# ProPrj_usb__2025-12-14-12-29-49.net
KiCad netlist of a schematic drawn in EasyEDA Pro
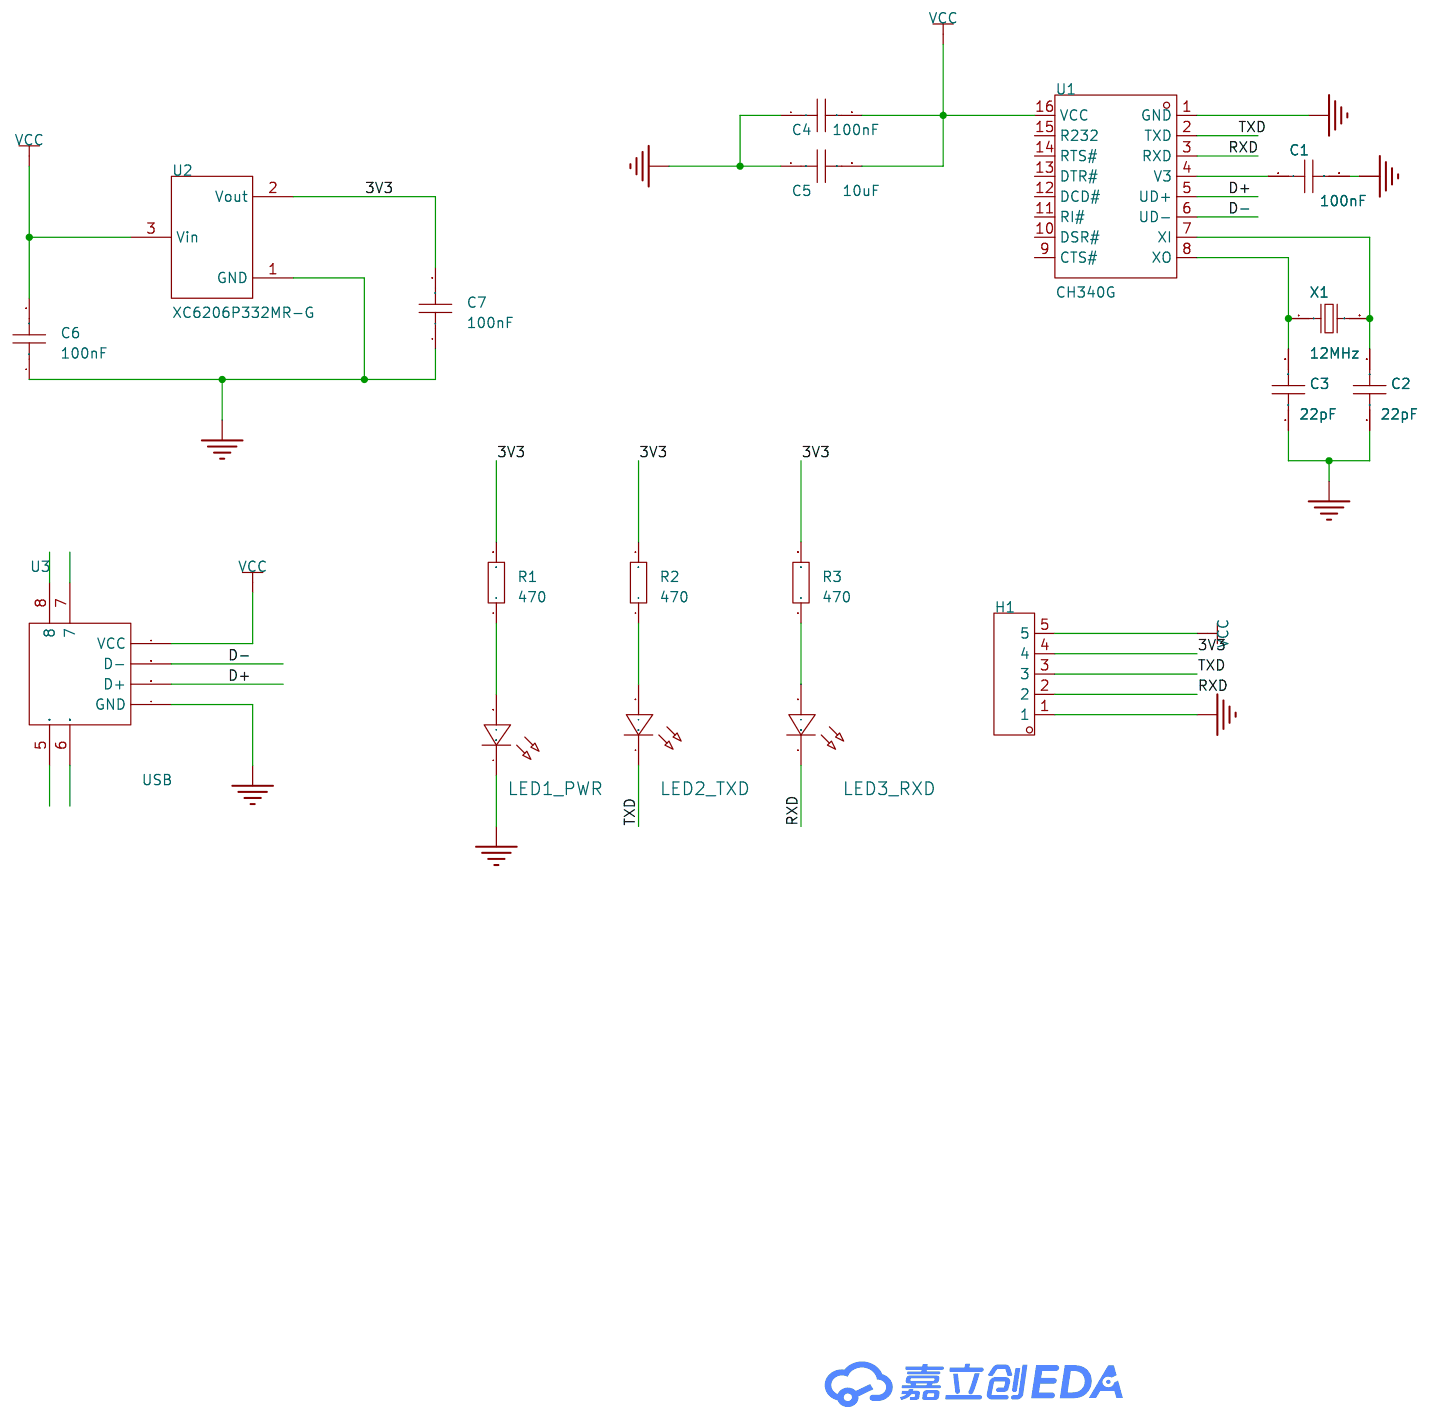
[diagram p0: schematic sheet]

(export (version "E")
  (design (tool "Eeschema 10.0.6"))
  (components
    (comp (ref "C1")
      (value "100nF")
      (footprint "easyedapro:C0603")
      (libsource (lib "easyedapro") (part "Capacitance"))
    )
    (comp (ref "C2")
      (value "22pF")
      (footprint "easyedapro:C0603")
      (libsource (lib "easyedapro") (part "Capacitance"))
    )
    (comp (ref "C3")
      (value "22pF")
      (footprint "easyedapro:C0603")
      (libsource (lib "easyedapro") (part "Capacitance"))
    )
    (comp (ref "C4")
      (value "100nF")
      (footprint "easyedapro:C0603")
      (libsource (lib "easyedapro") (part "Capacitance"))
    )
    (comp (ref "C5")
      (value "10uF")
      (footprint "easyedapro:C0603")
      (libsource (lib "easyedapro") (part "Capacitance"))
    )
    (comp (ref "C6")
      (value "100nF")
      (footprint "easyedapro:C0603")
      (libsource (lib "easyedapro") (part "Capacitance"))
    )
    (comp (ref "C7")
      (value "100nF")
      (footprint "easyedapro:C0603")
      (libsource (lib "easyedapro") (part "Capacitance"))
    )
    (comp (ref "H1")
      (value "~")
      (footprint "easyedapro:HDR-TH_5P-P2.54-V-M")
      (libsource (lib "easyedapro") (part "MTP125-1105S1"))
    )
    (comp (ref "LED1_PWR")
      (value "~")
      (footprint "easyedapro:LED_0603")
      (libsource (lib "easyedapro") (part "LED_R"))
    )
    (comp (ref "LED2_TXD")
      (value "~")
      (footprint "easyedapro:LED_0603")
      (libsource (lib "easyedapro") (part "LED_R"))
    )
    (comp (ref "LED3_RXD")
      (value "~")
      (footprint "easyedapro:LED_0603")
      (libsource (lib "easyedapro") (part "LED_R"))
    )
    (comp (ref "R1") (value "470") (footprint "easyedapro:R0603") (libsource (lib "easyedapro") (part "电阻")))
    (comp (ref "R2") (value "470") (footprint "easyedapro:R0603") (libsource (lib "easyedapro") (part "电阻")))
    (comp (ref "R3") (value "470") (footprint "easyedapro:R0603") (libsource (lib "easyedapro") (part "电阻")))
    (comp (ref "U1")
      (value "CH340G")
      (footprint "easyedapro:SOIC-16_L9.9-W3.9-P1.27-LS6.0-BL")
      (description "应用功能:USB转UART;接口协议:USB 2.0;数据速率:2Mbps;")
      (fields (field (name "Manufacturer") "WCH(南京沁恒)"))
      (libsource (lib "easyedapro") (part "CH340G"))
    )
    (comp (ref "U2")
      (value "XC6206P332MR-G")
      (footprint "easyedapro:SOT-23-3_L2.9-W1.6-P1.90-LS2.8-BR")
      (description "输出类型:固定;工作电压:6V;输出电压:3.3V;输出电流:200mA;电源纹波抑制比(PSRR):-;输出极性:正极;")
      (fields (field (name "Manufacturer") "TOREX(特瑞仕)"))
      (libsource (lib "easyedapro") (part "XC6206P332MR"))
    )
    (comp (ref "U3")
      (value "USB")
      (footprint "easyedapro:USB-SMD_USB_1")
      (libsource (lib "easyedapro") (part "USB"))
    )
    (comp (ref "X1")
      (value "12MHz")
      (footprint "easyedapro:CRYSTAL-SMD_L5.0-W3.2")
      (description "晶振类型:贴片晶振;频率:12MHz;常温频差:±20ppm;负载电容:20pF;频率稳定度:±30ppm;")
      (fields
        (field (name "Manufacturer Part") "XC53G2-12.000-F20LJDT")
        (field (name "Manufacturer") "HCI(杭晶)")
      )
      (libsource (lib "easyedapro") (part "XC53G2-12.000-F20LJDT"))
    )
  )
  (nets
    (net (code "1") (name "/3V3") (class "Default")
      (node (ref "C7") (pin "2") (pinfunction "2_2") (pintype "input"))
      (node (ref "H1") (pin "4") (pinfunction "4_4") (pintype "unspecified"))
      (node (ref "R1") (pin "2") (pinfunction "2_2") (pintype "input"))
      (node (ref "R2") (pin "2") (pinfunction "2_2") (pintype "input"))
      (node (ref "R3") (pin "2") (pinfunction "2_2") (pintype "input"))
      (node (ref "U2") (pin "2") (pinfunction "Vout_2") (pintype "unspecified"))
    )
    (net (code "2") (name "/D+") (class "Default")
      (node (ref "U1") (pin "5") (pinfunction "UD+_5") (pintype "unspecified"))
      (node (ref "U3") (pin "3") (pinfunction "D+_3") (pintype "input"))
    )
    (net (code "3") (name "/D-") (class "Default")
      (node (ref "U1") (pin "6") (pinfunction "UD-_6") (pintype "unspecified"))
      (node (ref "U3") (pin "2") (pinfunction "D-_2") (pintype "input"))
    )
    (net (code "4") (name "/RXD") (class "Default")
      (node (ref "H1") (pin "2") (pinfunction "2_2") (pintype "unspecified"))
      (node (ref "LED3_RXD") (pin "1") (pinfunction "C_1") (pintype "input"))
      (node (ref "U1") (pin "3") (pinfunction "RXD_3") (pintype "unspecified"))
    )
    (net (code "5") (name "/TXD") (class "Default")
      (node (ref "H1") (pin "3") (pinfunction "3_3") (pintype "unspecified"))
      (node (ref "LED2_TXD") (pin "1") (pinfunction "C_1") (pintype "input"))
      (node (ref "U1") (pin "2") (pinfunction "TXD_2") (pintype "unspecified"))
    )
    (net (code "6") (name "GND") (class "Default")
      (node (ref "C1") (pin "2") (pinfunction "2_2") (pintype "input"))
      (node (ref "C2") (pin "1") (pinfunction "1_1") (pintype "input"))
      (node (ref "C3") (pin "1") (pinfunction "1_1") (pintype "input"))
      (node (ref "C4") (pin "1") (pinfunction "1_1") (pintype "input"))
      (node (ref "C5") (pin "1") (pinfunction "1_1") (pintype "input"))
      (node (ref "C6") (pin "1") (pinfunction "1_1") (pintype "input"))
      (node (ref "C7") (pin "1") (pinfunction "1_1") (pintype "input"))
      (node (ref "H1") (pin "1") (pinfunction "1_1") (pintype "unspecified"))
      (node (ref "LED1_PWR") (pin "1") (pinfunction "C_1") (pintype "input"))
      (node (ref "U1") (pin "1") (pinfunction "GND_1") (pintype "unspecified"))
      (node (ref "U2") (pin "1") (pinfunction "GND_1") (pintype "unspecified"))
      (node (ref "U3") (pin "4") (pinfunction "GND_4") (pintype "input"))
    )
    (net (code "7") (name "Net-(LED1_PWR-A)") (class "Default")
      (node (ref "LED1_PWR") (pin "2") (pinfunction "A_2") (pintype "input"))
      (node (ref "R1") (pin "1") (pinfunction "1_1") (pintype "input"))
    )
    (net (code "8") (name "Net-(LED2_TXD-A)") (class "Default")
      (node (ref "LED2_TXD") (pin "2") (pinfunction "A_2") (pintype "input"))
      (node (ref "R2") (pin "1") (pinfunction "1_1") (pintype "input"))
    )
    (net (code "9") (name "Net-(LED3_RXD-A)") (class "Default")
      (node (ref "LED3_RXD") (pin "2") (pinfunction "A_2") (pintype "input"))
      (node (ref "R3") (pin "1") (pinfunction "1_1") (pintype "input"))
    )
    (net (code "10") (name "Net-(U1-V3)") (class "Default")
      (node (ref "C1") (pin "1") (pinfunction "1_1") (pintype "input"))
      (node (ref "U1") (pin "4") (pinfunction "V3_4") (pintype "unspecified"))
    )
    (net (code "11") (name "Net-(U1-XI)") (class "Default")
      (node (ref "C2") (pin "2") (pinfunction "2_2") (pintype "input"))
      (node (ref "U1") (pin "7") (pinfunction "XI_7") (pintype "unspecified"))
      (node (ref "X1") (pin "2") (pinfunction "2_2") (pintype "unspecified"))
    )
    (net (code "12") (name "Net-(U1-XO)") (class "Default")
      (node (ref "C3") (pin "2") (pinfunction "2_2") (pintype "input"))
      (node (ref "U1") (pin "8") (pinfunction "XO_8") (pintype "unspecified"))
      (node (ref "X1") (pin "1") (pinfunction "1_1") (pintype "unspecified"))
    )
    (net (code "13") (name "VCC") (class "Default")
      (node (ref "C4") (pin "2") (pinfunction "2_2") (pintype "input"))
      (node (ref "C5") (pin "2") (pinfunction "2_2") (pintype "input"))
      (node (ref "C6") (pin "2") (pinfunction "2_2") (pintype "input"))
      (node (ref "H1") (pin "5") (pinfunction "5_5") (pintype "unspecified"))
      (node (ref "U1") (pin "16") (pinfunction "VCC_16") (pintype "unspecified"))
      (node (ref "U2") (pin "3") (pinfunction "Vin_3") (pintype "unspecified"))
      (node (ref "U3") (pin "1") (pinfunction "VCC_1") (pintype "input"))
    )
    (net (code "14") (name "unconnected-(U1-CTS#-Pad9)") (class "Default")
      (node (ref "U1") (pin "9") (pinfunction "CTS#_9") (pintype "unspecified"))
    )
    (net (code "15") (name "unconnected-(U1-DCD#-Pad12)") (class "Default")
      (node (ref "U1") (pin "12") (pinfunction "DCD#_12") (pintype "unspecified"))
    )
    (net (code "16") (name "unconnected-(U1-DSR#-Pad10)") (class "Default")
      (node (ref "U1") (pin "10") (pinfunction "DSR#_10") (pintype "unspecified"))
    )
    (net (code "17") (name "unconnected-(U1-DTR#-Pad13)") (class "Default")
      (node (ref "U1") (pin "13") (pinfunction "DTR#_13") (pintype "unspecified"))
    )
    (net (code "18") (name "unconnected-(U1-R232-Pad15)") (class "Default")
      (node (ref "U1") (pin "15") (pinfunction "R232_15") (pintype "unspecified"))
    )
    (net (code "19") (name "unconnected-(U1-RI#-Pad11)") (class "Default")
      (node (ref "U1") (pin "11") (pinfunction "RI#_11") (pintype "unspecified"))
    )
    (net (code "20") (name "unconnected-(U1-RTS#-Pad14)") (class "Default")
      (node (ref "U1") (pin "14") (pinfunction "RTS#_14") (pintype "unspecified"))
    )
    (net (code "21") (name "unconnected-(U3-Pad7)") (class "Default")
      (node (ref "U3") (pin "7") (pinfunction "7_7") (pintype "unspecified"))
    )
    (net (code "22") (name "unconnected-(U3-Pad8)") (class "Default")
      (node (ref "U3") (pin "8") (pinfunction "8_8") (pintype "unspecified"))
    )
    (net (code "23") (name "unconnected-(U3-SH1-Pad5)") (class "Default")
      (node (ref "U3") (pin "5") (pinfunction "SH1_5") (pintype "unspecified"))
    )
    (net (code "24") (name "unconnected-(U3-SH2-Pad6)") (class "Default")
      (node (ref "U3") (pin "6") (pinfunction "SH2_6") (pintype "unspecified"))
    )
  )
)
